# Ethernet.net
KiCad netlist of a schematic drawn in Altium Designer
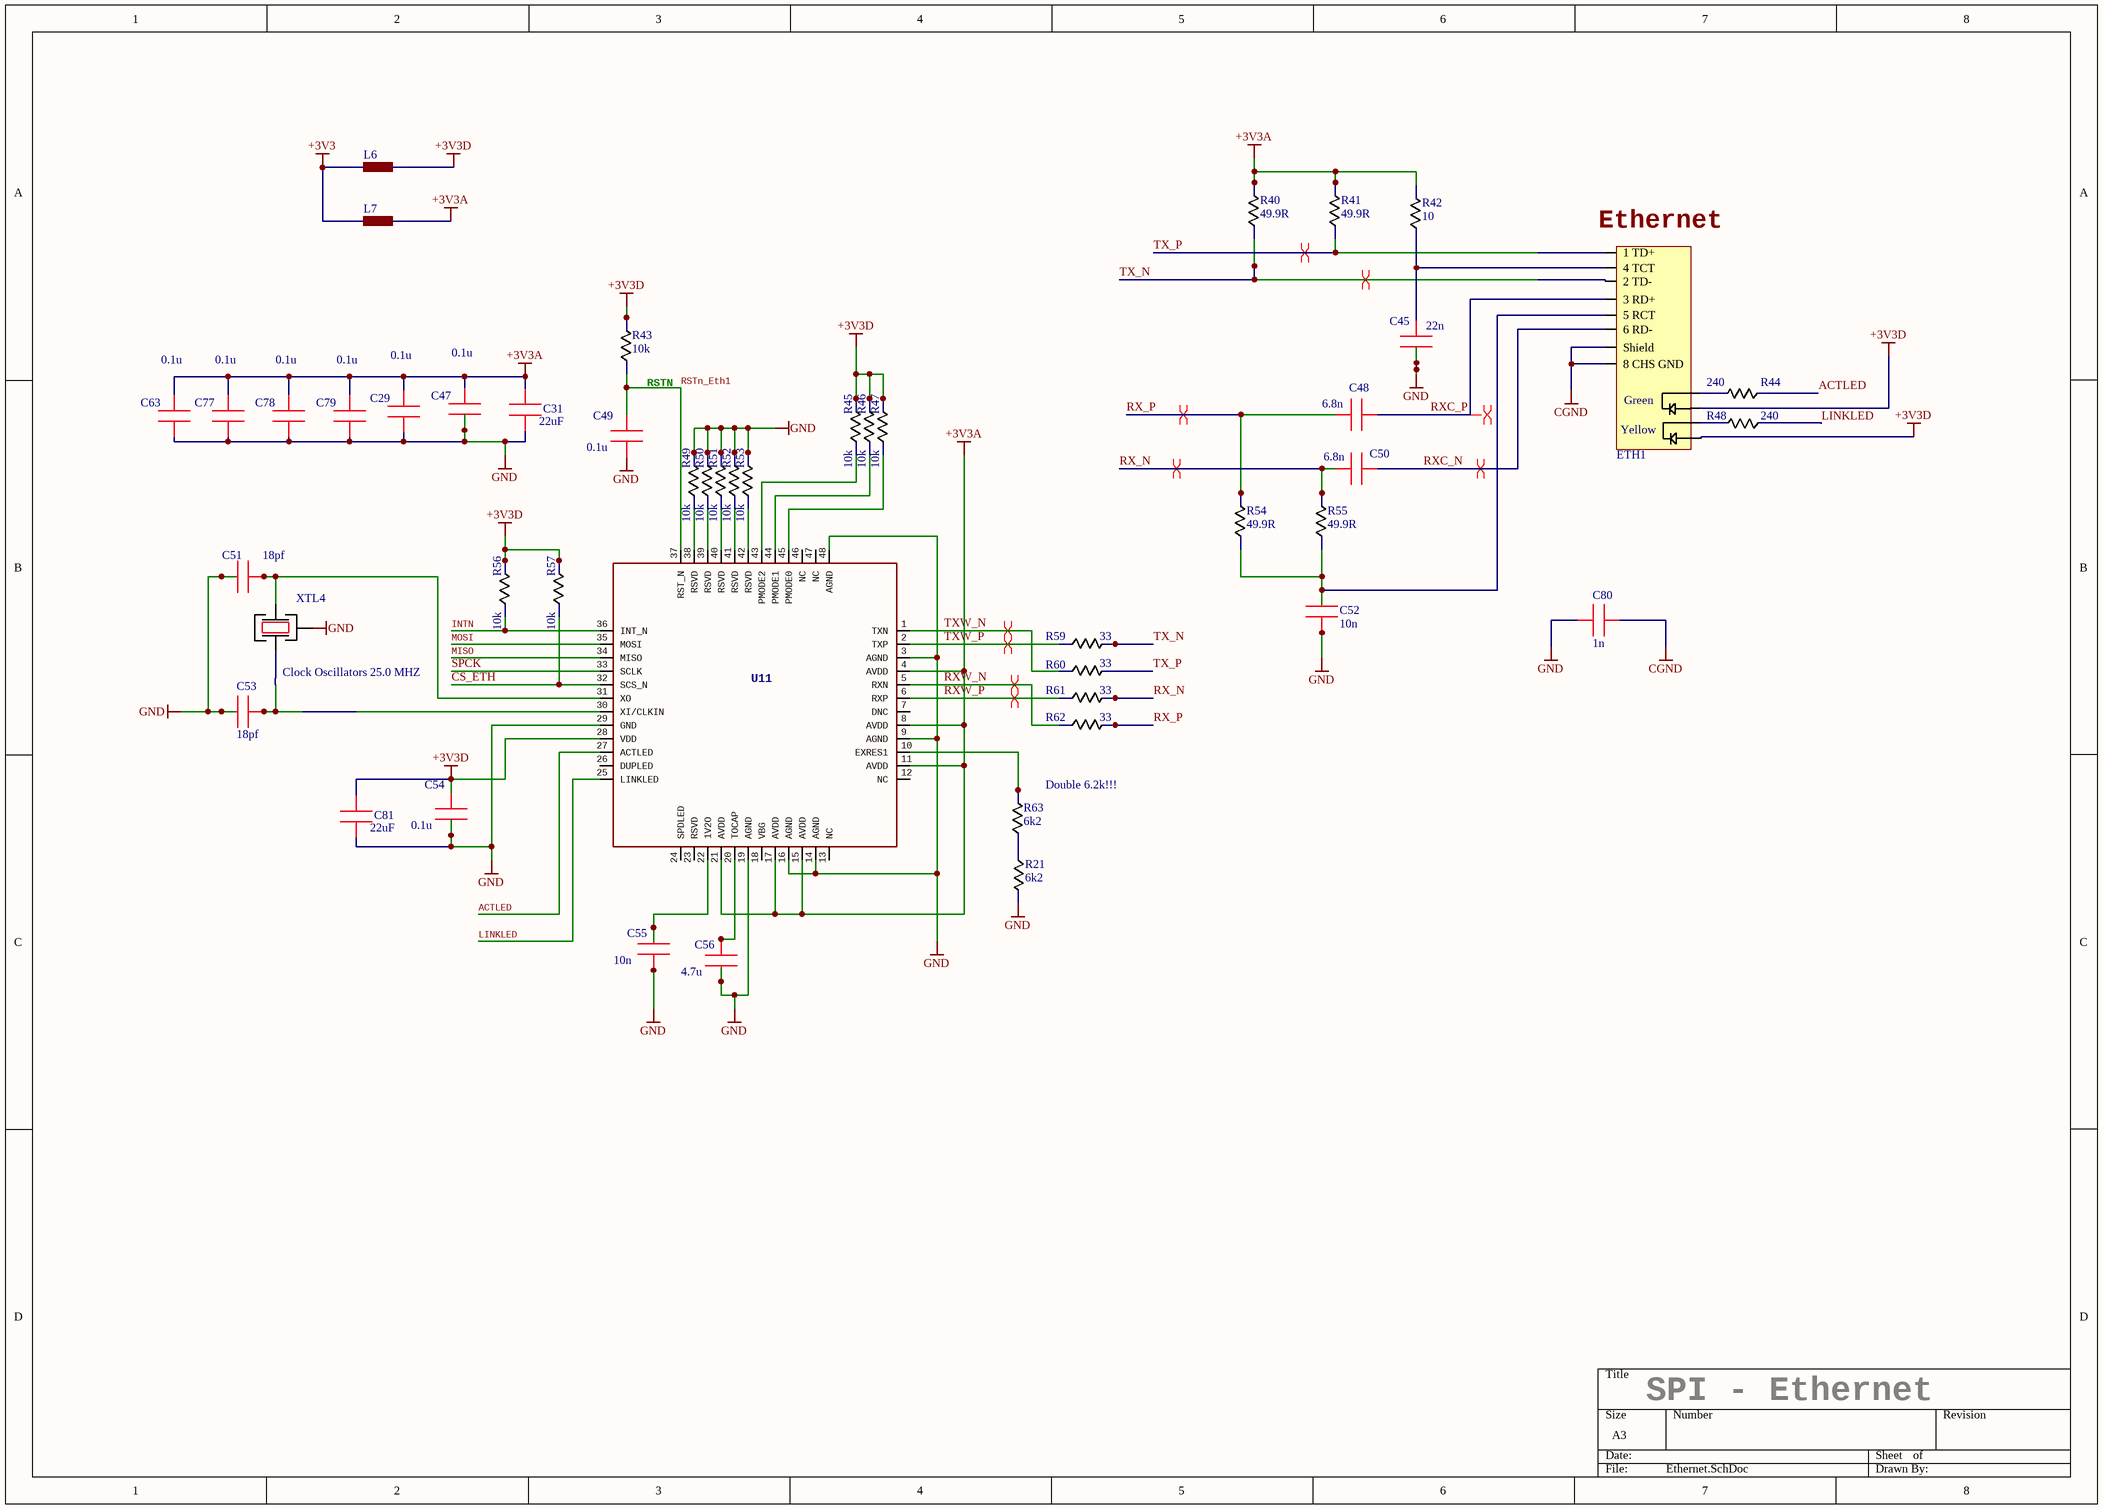
[diagram p0: Ethernet.SchDoc]

(export (version "E")
  (design (tool "Eeschema 10.0.6"))
  (components
    (comp (ref "C29")
      (value "0.1u")
      (footprint "0603")
      (fields (field (name "PART NUMBER") "GRM188R72A104KA35D"))
      (libsource (lib "kontr") (part "0603 CAP"))
    )
    (comp (ref "C31")
      (value "22uF")
      (footprint "1206")
      (fields (field (name "PART NUMBER") "CC1206KKX5R7BB226"))
      (libsource (lib "kontr") (part "0805 Cap"))
    )
    (comp (ref "C45")
      (value "22n")
      (footprint "0603")
      (fields (field (name "PART NUMBER") "GRM188R71H223KA01D"))
      (libsource (lib "kontr") (part "0603 CAP"))
    )
    (comp (ref "C47")
      (value "0.1u")
      (footprint "0603")
      (fields (field (name "PART NUMBER") "GRM188R72A104KA35D"))
      (libsource (lib "kontr") (part "0603 CAP"))
    )
    (comp (ref "C48")
      (value "6.8n")
      (footprint "0603")
      (fields (field (name "PART NUMBER") "CC0603KRX7R9BB682"))
      (libsource (lib "kontr") (part "0603 CAP"))
    )
    (comp (ref "C49")
      (value "0.1u")
      (footprint "0603")
      (fields (field (name "PART NUMBER") "GRM188R72A104KA35D"))
      (libsource (lib "kontr") (part "0603 CAP"))
    )
    (comp (ref "C50")
      (value "6.8n")
      (footprint "0603")
      (fields (field (name "PART NUMBER") "CC0603KRX7R9BB682"))
      (libsource (lib "kontr") (part "0603 CAP"))
    )
    (comp (ref "C51")
      (value "18pf")
      (footprint "0603")
      (fields (field (name "PART NUMBER") "GRM1885C1H180JA01D"))
      (libsource (lib "kontr") (part "0603 CAP"))
    )
    (comp (ref "C52")
      (value "10n")
      (footprint "0603")
      (fields (field (name "PART NUMBER") "CC0603JRX7R9BB103"))
      (libsource (lib "kontr") (part "0603 CAP"))
    )
    (comp (ref "C53")
      (value "18pf")
      (footprint "0603")
      (fields (field (name "PART NUMBER") "GRM1885C1H180JA01D"))
      (libsource (lib "kontr") (part "0603 CAP"))
    )
    (comp (ref "C54")
      (value "0.1u")
      (footprint "0603")
      (fields (field (name "PART NUMBER") "GRM188R72A104KA35D"))
      (libsource (lib "kontr") (part "0603 CAP"))
    )
    (comp (ref "C55")
      (value "10n")
      (footprint "0603")
      (fields (field (name "PART NUMBER") "CC0603JRX7R9BB103"))
      (libsource (lib "kontr") (part "0603 CAP"))
    )
    (comp (ref "C56")
      (value "4.7u")
      (footprint "0603")
      (fields (field (name "PART NUMBER") "CC0603KRX5R7BB475"))
      (libsource (lib "kontr") (part "0603 CAP"))
    )
    (comp (ref "C63")
      (value "0.1u")
      (footprint "0603")
      (fields (field (name "PART NUMBER") "GRM188R72A104KA35D"))
      (libsource (lib "kontr") (part "0603 CAP"))
    )
    (comp (ref "C77")
      (value "0.1u")
      (footprint "0603")
      (fields (field (name "PART NUMBER") "GRM188R72A104KA35D"))
      (libsource (lib "kontr") (part "0603 CAP"))
    )
    (comp (ref "C78")
      (value "0.1u")
      (footprint "0603")
      (fields (field (name "PART NUMBER") "GRM188R72A104KA35D"))
      (libsource (lib "kontr") (part "0603 CAP"))
    )
    (comp (ref "C79")
      (value "0.1u")
      (footprint "0603")
      (fields (field (name "PART NUMBER") "GRM188R72A104KA35D"))
      (libsource (lib "kontr") (part "0603 CAP"))
    )
    (comp (ref "C80")
      (value "1n")
      (footprint "1206")
      (fields (field (name "PART NUMBER") "CC1206KKX7RDBB102"))
      (libsource (lib "kontr") (part "0603 CAP"))
    )
    (comp (ref "C81")
      (value "22uF")
      (footprint "1206")
      (fields (field (name "PART NUMBER") "CC1206KKX5R7BB226"))
      (libsource (lib "kontr") (part "0805 Cap"))
    )
    (comp (ref "ETH1")
      (value "~")
      (footprint "RJ45")
      (fields (field (name "PART NUMBER") "J0011D21BNL"))
      (libsource (lib "kontr") (part "J0011D21BNL"))
    )
    (comp (ref "L6")
      (value "~")
      (footprint "0805")
      (fields (field (name "PART NUMBER") "BLM41PG102SN1L"))
      (libsource (lib "altium-import") (part "root_0__kontr.SCHLIB"))
    )
    (comp (ref "L7")
      (value "~")
      (footprint "0805")
      (fields (field (name "PART NUMBER") "BLM41PG102SN1L"))
      (libsource (lib "altium-import") (part "root_0__kontr.SCHLIB"))
    )
    (comp (ref "R21")
      (value "6k2")
      (footprint "0603")
      (fields (field (name "PART NUMBER") "RC0603JR-076K2L"))
      (libsource (lib "kontr") (part "Resistor 0805"))
    )
    (comp (ref "R40")
      (value "49.9R")
      (footprint "0603")
      (fields (field (name "PART NUMBER") "RC0603FR-0749R9"))
      (libsource (lib "kontr") (part "0603 RES"))
    )
    (comp (ref "R41")
      (value "49.9R")
      (footprint "0603")
      (fields (field (name "PART NUMBER") "RC0603FR-0749R9"))
      (libsource (lib "kontr") (part "0603 RES"))
    )
    (comp (ref "R42")
      (value "10")
      (footprint "0603")
      (fields (field (name "PART NUMBER") "CRCW060310R0FKEA"))
      (libsource (lib "kontr") (part "0603 RES"))
    )
    (comp (ref "R43")
      (value "10k")
      (footprint "0603")
      (fields (field (name "PART NUMBER") "RC0603JR-0710K"))
      (libsource (lib "kontr") (part "0603 RES"))
    )
    (comp (ref "R44")
      (value "240")
      (footprint "0603")
      (fields (field (name "PART NUMBER") "RC0603FR-07240RL"))
      (libsource (lib "kontr") (part "0603 RES"))
    )
    (comp (ref "R45")
      (value "10k")
      (footprint "0603")
      (fields (field (name "PART NUMBER") "RC0603JR-0710K"))
      (libsource (lib "kontr") (part "0603 RES"))
    )
    (comp (ref "R46")
      (value "10k")
      (footprint "0603")
      (fields (field (name "PART NUMBER") "RC0603JR-0710K"))
      (libsource (lib "kontr") (part "0603 RES"))
    )
    (comp (ref "R47")
      (value "10k")
      (footprint "0603")
      (fields (field (name "PART NUMBER") "RC0603JR-0710K"))
      (libsource (lib "kontr") (part "0603 RES"))
    )
    (comp (ref "R48")
      (value "240")
      (footprint "0603")
      (fields (field (name "PART NUMBER") "RC0603FR-07240RL"))
      (libsource (lib "kontr") (part "0603 RES"))
    )
    (comp (ref "R49")
      (value "10k")
      (footprint "0603")
      (fields (field (name "PART NUMBER") "RC0603JR-0710K"))
      (libsource (lib "kontr") (part "0603 RES"))
    )
    (comp (ref "R50")
      (value "10k")
      (footprint "0603")
      (fields (field (name "PART NUMBER") "RC0603JR-0710K"))
      (libsource (lib "kontr") (part "0603 RES"))
    )
    (comp (ref "R51")
      (value "10k")
      (footprint "0603")
      (fields (field (name "PART NUMBER") "RC0603JR-0710K"))
      (libsource (lib "kontr") (part "0603 RES"))
    )
    (comp (ref "R52")
      (value "10k")
      (footprint "0603")
      (fields (field (name "PART NUMBER") "RC0603JR-0710K"))
      (libsource (lib "kontr") (part "0603 RES"))
    )
    (comp (ref "R53")
      (value "10k")
      (footprint "0603")
      (fields (field (name "PART NUMBER") "RC0603JR-0710K"))
      (libsource (lib "kontr") (part "0603 RES"))
    )
    (comp (ref "R54")
      (value "49.9R")
      (footprint "0603")
      (fields (field (name "PART NUMBER") "RC0603FR-0749R9"))
      (libsource (lib "kontr") (part "0603 RES"))
    )
    (comp (ref "R55")
      (value "49.9R")
      (footprint "0603")
      (fields (field (name "PART NUMBER") "RC0603FR-0749R9"))
      (libsource (lib "kontr") (part "0603 RES"))
    )
    (comp (ref "R56")
      (value "10k")
      (footprint "0603")
      (fields (field (name "PART NUMBER") "RC0603JR-0710K"))
      (libsource (lib "kontr") (part "0603 RES"))
    )
    (comp (ref "R57")
      (value "10k")
      (footprint "0603")
      (fields (field (name "PART NUMBER") "RC0603JR-0710K"))
      (libsource (lib "kontr") (part "0603 RES"))
    )
    (comp (ref "R59")
      (value "33")
      (footprint "0603")
      (fields (field (name "PART NUMBER") "RC0603FR-0733RL"))
      (libsource (lib "kontr") (part "0603 RES"))
    )
    (comp (ref "R60")
      (value "33")
      (footprint "0603")
      (fields (field (name "PART NUMBER") "RC0603FR-0733RL"))
      (libsource (lib "kontr") (part "0603 RES"))
    )
    (comp (ref "R61")
      (value "33")
      (footprint "0603")
      (fields (field (name "PART NUMBER") "RC0603FR-0733RL"))
      (libsource (lib "kontr") (part "0603 RES"))
    )
    (comp (ref "R62")
      (value "33")
      (footprint "0603")
      (fields (field (name "PART NUMBER") "RC0603FR-0733RL"))
      (libsource (lib "kontr") (part "0603 RES"))
    )
    (comp (ref "R63")
      (value "6k2")
      (footprint "0603")
      (fields (field (name "PART NUMBER") "RC0603JR-076K2L"))
      (libsource (lib "kontr") (part "0603 RES"))
    )
    (comp (ref "U11")
      (value "~")
      (footprint "LQFP 48")
      (fields (field (name "PART NUMBER") "W5500"))
      (libsource (lib "W5500") (part "W5500"))
    )
    (comp (ref "XTL4")
      (value "~")
      (footprint "KX-7 XTAL")
      (fields
        (field (name "PART DESCRIPTION") "Clock Oscillators 25.0 MHZ")
        (field (name "PART NUMBER") "Geyer KX-7 25.0 MHz")
      )
      (libsource (lib "kontr") (part "KX-7"))
    )
  )
  (nets
    (net (code "1") (name "+3V3") (class "Default")
      (node (ref "L6") (pin "1") (pintype "passive"))
      (node (ref "L7") (pin "1") (pintype "passive"))
    )
    (net (code "2") (name "+3V3A") (class "Default")
      (node (ref "C29") (pin "1") (pinfunction "1_1") (pintype "passive"))
      (node (ref "C31") (pin "2") (pinfunction "2_2") (pintype "passive"))
      (node (ref "C47") (pin "1") (pinfunction "1_1") (pintype "passive"))
      (node (ref "C63") (pin "1") (pinfunction "1_1") (pintype "passive"))
      (node (ref "C77") (pin "1") (pinfunction "1_1") (pintype "passive"))
      (node (ref "C78") (pin "1") (pinfunction "1_1") (pintype "passive"))
      (node (ref "C79") (pin "1") (pinfunction "1_1") (pintype "passive"))
      (node (ref "L7") (pin "2") (pintype "passive"))
      (node (ref "R40") (pin "2") (pintype "passive"))
      (node (ref "R41") (pin "2") (pintype "passive"))
      (node (ref "R42") (pin "2") (pintype "passive"))
      (node (ref "U11") (pin "11") (pinfunction "AVDD_11") (pintype "passive"))
      (node (ref "U11") (pin "15") (pinfunction "AVDD_15") (pintype "passive"))
      (node (ref "U11") (pin "17") (pinfunction "AVDD_17") (pintype "passive"))
      (node (ref "U11") (pin "21") (pinfunction "AVDD_21") (pintype "passive"))
      (node (ref "U11") (pin "4") (pinfunction "AVDD_4") (pintype "passive"))
      (node (ref "U11") (pin "8") (pinfunction "AVDD_8") (pintype "passive"))
    )
    (net (code "3") (name "+3V3D") (class "Default")
      (node (ref "C54") (pin "1") (pinfunction "1_1") (pintype "passive"))
      (node (ref "C81") (pin "2") (pinfunction "2_2") (pintype "passive"))
      (node (ref "ETH1") (pin "12") (pinfunction "LDYE_12") (pintype "passive"))
      (node (ref "ETH1") (pin "9") (pinfunction "LDGr_9") (pintype "passive"))
      (node (ref "L6") (pin "2") (pintype "passive"))
      (node (ref "R43") (pin "2") (pintype "passive"))
      (node (ref "R45") (pin "2") (pintype "passive"))
      (node (ref "R46") (pin "2") (pintype "passive"))
      (node (ref "R47") (pin "2") (pintype "passive"))
      (node (ref "R56") (pin "2") (pintype "passive"))
      (node (ref "R57") (pin "2") (pintype "passive"))
      (node (ref "U11") (pin "28") (pinfunction "VDD_28") (pintype "passive"))
    )
    (net (code "4") (name "/ACTLED") (class "Default")
      (node (ref "R44") (pin "1") (pintype "passive"))
      (node (ref "U11") (pin "27") (pinfunction "ACTLED_27") (pintype "passive"))
    )
    (net (code "5") (name "/CS_ETH") (class "Default")
      (node (ref "R57") (pin "1") (pintype "passive"))
      (node (ref "U11") (pin "32") (pinfunction "SCS_N_32") (pintype "passive"))
    )
    (net (code "6") (name "/INTN") (class "Default")
      (node (ref "R56") (pin "1") (pintype "passive"))
      (node (ref "U11") (pin "36") (pinfunction "INT_N_36") (pintype "passive"))
    )
    (net (code "7") (name "/LINKLED") (class "Default")
      (node (ref "R48") (pin "1") (pintype "passive"))
      (node (ref "U11") (pin "25") (pinfunction "LINKLED_25") (pintype "passive"))
    )
    (net (code "8") (name "/MISO") (class "Default")
      (node (ref "U11") (pin "34") (pinfunction "MISO_34") (pintype "passive"))
    )
    (net (code "9") (name "/MOSI") (class "Default")
      (node (ref "U11") (pin "35") (pinfunction "MOSI_35") (pintype "passive"))
    )
    (net (code "10") (name "/RSTn_Eth1") (class "Default")
      (node (ref "C49") (pin "1") (pinfunction "1_1") (pintype "passive"))
      (node (ref "R43") (pin "1") (pintype "passive"))
      (node (ref "U11") (pin "37") (pinfunction "RST_N_37") (pintype "passive"))
    )
    (net (code "11") (name "/RXC_N") (class "Default")
      (node (ref "C50") (pin "2") (pinfunction "2_2") (pintype "passive"))
      (node (ref "ETH1") (pin "6") (pinfunction "6_RD-_6") (pintype "passive"))
    )
    (net (code "12") (name "/RXC_P") (class "Default")
      (node (ref "C48") (pin "2") (pinfunction "2_2") (pintype "passive"))
      (node (ref "ETH1") (pin "3") (pinfunction "3_RD+_3") (pintype "passive"))
    )
    (net (code "13") (name "/RXW_N") (class "Default")
      (node (ref "R62") (pin "1") (pintype "passive"))
      (node (ref "U11") (pin "5") (pinfunction "RXN_5") (pintype "passive"))
    )
    (net (code "14") (name "/RXW_P") (class "Default")
      (node (ref "R61") (pin "1") (pintype "passive"))
      (node (ref "U11") (pin "6") (pinfunction "RXP_6") (pintype "passive"))
    )
    (net (code "15") (name "/RX_N") (class "Default")
      (node (ref "C50") (pin "1") (pinfunction "1_1") (pintype "passive"))
      (node (ref "R55") (pin "2") (pintype "passive"))
      (node (ref "R61") (pin "2") (pintype "passive"))
    )
    (net (code "16") (name "/RX_P") (class "Default")
      (node (ref "C48") (pin "1") (pinfunction "1_1") (pintype "passive"))
      (node (ref "R54") (pin "2") (pintype "passive"))
      (node (ref "R62") (pin "2") (pintype "passive"))
    )
    (net (code "17") (name "/SPCK") (class "Default")
      (node (ref "U11") (pin "33") (pinfunction "SCLK_33") (pintype "passive"))
    )
    (net (code "18") (name "/TXW_N") (class "Default")
      (node (ref "R60") (pin "1") (pintype "passive"))
      (node (ref "U11") (pin "1") (pinfunction "TXN_1") (pintype "passive"))
    )
    (net (code "19") (name "/TXW_P") (class "Default")
      (node (ref "R59") (pin "1") (pintype "passive"))
      (node (ref "U11") (pin "2") (pinfunction "TXP_2") (pintype "passive"))
    )
    (net (code "20") (name "/TX_N") (class "Default")
      (node (ref "ETH1") (pin "2") (pinfunction "2_TD-_2") (pintype "passive"))
      (node (ref "R40") (pin "1") (pintype "passive"))
      (node (ref "R59") (pin "2") (pintype "passive"))
    )
    (net (code "21") (name "/TX_P") (class "Default")
      (node (ref "ETH1") (pin "1") (pinfunction "1_TD+_1") (pintype "passive"))
      (node (ref "R41") (pin "1") (pintype "passive"))
      (node (ref "R60") (pin "2") (pintype "passive"))
    )
    (net (code "22") (name "CGND") (class "Default")
      (node (ref "C80") (pin "2") (pinfunction "2_2") (pintype "passive"))
      (node (ref "ETH1") (pin "8") (pinfunction "8_CHS_GND_8") (pintype "passive"))
      (node (ref "ETH1") (pin "SHIELD") (pinfunction "Shield_SHIELD") (pintype "passive"))
    )
    (net (code "23") (name "GND") (class "Default")
      (node (ref "C29") (pin "2") (pinfunction "2_2") (pintype "passive"))
      (node (ref "C31") (pin "1") (pinfunction "1_1") (pintype "passive"))
      (node (ref "C45") (pin "2") (pinfunction "2_2") (pintype "passive"))
      (node (ref "C47") (pin "2") (pinfunction "2_2") (pintype "passive"))
      (node (ref "C49") (pin "2") (pinfunction "2_2") (pintype "passive"))
      (node (ref "C51") (pin "1") (pinfunction "1_1") (pintype "passive"))
      (node (ref "C52") (pin "2") (pinfunction "2_2") (pintype "passive"))
      (node (ref "C53") (pin "1") (pinfunction "1_1") (pintype "passive"))
      (node (ref "C54") (pin "2") (pinfunction "2_2") (pintype "passive"))
      (node (ref "C55") (pin "2") (pinfunction "2_2") (pintype "passive"))
      (node (ref "C56") (pin "2") (pinfunction "2_2") (pintype "passive"))
      (node (ref "C63") (pin "2") (pinfunction "2_2") (pintype "passive"))
      (node (ref "C77") (pin "2") (pinfunction "2_2") (pintype "passive"))
      (node (ref "C78") (pin "2") (pinfunction "2_2") (pintype "passive"))
      (node (ref "C79") (pin "2") (pinfunction "2_2") (pintype "passive"))
      (node (ref "C80") (pin "1") (pinfunction "1_1") (pintype "passive"))
      (node (ref "C81") (pin "1") (pinfunction "1_1") (pintype "passive"))
      (node (ref "R21") (pin "2") (pintype "passive"))
      (node (ref "R49") (pin "2") (pintype "passive"))
      (node (ref "R50") (pin "2") (pintype "passive"))
      (node (ref "R51") (pin "2") (pintype "passive"))
      (node (ref "R52") (pin "2") (pintype "passive"))
      (node (ref "R53") (pin "2") (pintype "passive"))
      (node (ref "U11") (pin "14") (pinfunction "AGND_14") (pintype "passive"))
      (node (ref "U11") (pin "16") (pinfunction "AGND_16") (pintype "passive"))
      (node (ref "U11") (pin "19") (pinfunction "AGND_19") (pintype "passive"))
      (node (ref "U11") (pin "29") (pinfunction "GND_29") (pintype "passive"))
      (node (ref "U11") (pin "3") (pinfunction "AGND_3") (pintype "passive"))
      (node (ref "U11") (pin "48") (pinfunction "AGND_48") (pintype "passive"))
      (node (ref "U11") (pin "9") (pinfunction "AGND_9") (pintype "passive"))
      (node (ref "XTL4") (pin "2") (pinfunction "2_2") (pintype "passive"))
    )
    (net (code "24") (name "Net-(ETH1-4_TCT)") (class "Default")
      (node (ref "C45") (pin "1") (pinfunction "1_1") (pintype "passive"))
      (node (ref "ETH1") (pin "4") (pinfunction "4_TCT_4") (pintype "passive"))
      (node (ref "R42") (pin "1") (pintype "passive"))
    )
    (net (code "25") (name "Net-(ETH1-5_RCT)") (class "Default")
      (node (ref "C52") (pin "1") (pinfunction "1_1") (pintype "passive"))
      (node (ref "ETH1") (pin "5") (pinfunction "5_RCT_5") (pintype "passive"))
      (node (ref "R54") (pin "1") (pintype "passive"))
      (node (ref "R55") (pin "1") (pintype "passive"))
    )
    (net (code "26") (name "Net-(ETH1-LDGr-Pad10)") (class "Default")
      (node (ref "ETH1") (pin "10") (pinfunction "LDGr_10") (pintype "passive"))
      (node (ref "R44") (pin "2") (pintype "passive"))
    )
    (net (code "27") (name "Net-(ETH1-LDYE-Pad11)") (class "Default")
      (node (ref "ETH1") (pin "11") (pinfunction "LDYE_11") (pintype "passive"))
      (node (ref "R48") (pin "2") (pintype "passive"))
    )
    (net (code "28") (name "Net-(R21-Pad1)") (class "Default")
      (node (ref "R21") (pin "1") (pintype "passive"))
      (node (ref "R63") (pin "1") (pintype "passive"))
    )
    (net (code "29") (name "Net-(R49-Pad1)") (class "Default")
      (node (ref "R49") (pin "1") (pintype "passive"))
      (node (ref "U11") (pin "38") (pinfunction "RSVD_38") (pintype "passive"))
    )
    (net (code "30") (name "Net-(R50-Pad1)") (class "Default")
      (node (ref "R50") (pin "1") (pintype "passive"))
      (node (ref "U11") (pin "39") (pinfunction "RSVD_39") (pintype "passive"))
    )
    (net (code "31") (name "Net-(R51-Pad1)") (class "Default")
      (node (ref "R51") (pin "1") (pintype "passive"))
      (node (ref "U11") (pin "40") (pinfunction "RSVD_40") (pintype "passive"))
    )
    (net (code "32") (name "Net-(R52-Pad1)") (class "Default")
      (node (ref "R52") (pin "1") (pintype "passive"))
      (node (ref "U11") (pin "41") (pinfunction "RSVD_41") (pintype "passive"))
    )
    (net (code "33") (name "Net-(R53-Pad1)") (class "Default")
      (node (ref "R53") (pin "1") (pintype "passive"))
      (node (ref "U11") (pin "42") (pinfunction "RSVD_42") (pintype "passive"))
    )
    (net (code "34") (name "Net-(U11-1V2O)") (class "Default")
      (node (ref "C55") (pin "1") (pinfunction "1_1") (pintype "passive"))
      (node (ref "U11") (pin "22") (pinfunction "1V2O_22") (pintype "passive"))
    )
    (net (code "35") (name "Net-(U11-EXRES1)") (class "Default")
      (node (ref "R63") (pin "2") (pintype "passive"))
      (node (ref "U11") (pin "10") (pinfunction "EXRES1_10") (pintype "passive"))
    )
    (net (code "36") (name "Net-(U11-PMODE0)") (class "Default")
      (node (ref "R47") (pin "1") (pintype "passive"))
      (node (ref "U11") (pin "45") (pinfunction "PMODE0_45") (pintype "passive"))
    )
    (net (code "37") (name "Net-(U11-PMODE1)") (class "Default")
      (node (ref "R46") (pin "1") (pintype "passive"))
      (node (ref "U11") (pin "44") (pinfunction "PMODE1_44") (pintype "passive"))
    )
    (net (code "38") (name "Net-(U11-PMODE2)") (class "Default")
      (node (ref "R45") (pin "1") (pintype "passive"))
      (node (ref "U11") (pin "43") (pinfunction "PMODE2_43") (pintype "passive"))
    )
    (net (code "39") (name "Net-(U11-TOCAP)") (class "Default")
      (node (ref "C56") (pin "1") (pinfunction "1_1") (pintype "passive"))
      (node (ref "U11") (pin "20") (pinfunction "TOCAP_20") (pintype "passive"))
    )
    (net (code "40") (name "Net-(U11-XI{slash}CLKIN)") (class "Default")
      (node (ref "C53") (pin "2") (pinfunction "2_2") (pintype "passive"))
      (node (ref "U11") (pin "30") (pinfunction "XI/CLKIN_30") (pintype "passive"))
      (node (ref "XTL4") (pin "1") (pinfunction "5_1") (pintype "passive"))
    )
    (net (code "41") (name "Net-(U11-XO)") (class "Default")
      (node (ref "C51") (pin "2") (pinfunction "2_2") (pintype "passive"))
      (node (ref "U11") (pin "31") (pinfunction "XO_31") (pintype "passive"))
      (node (ref "XTL4") (pin "3") (pinfunction "5_3") (pintype "passive"))
    )
    (net (code "42") (name "unconnected-(U11-DNC-Pad7)") (class "Default")
      (node (ref "U11") (pin "7") (pinfunction "DNC_7") (pintype "passive"))
    )
    (net (code "43") (name "unconnected-(U11-DUPLED-Pad26)") (class "Default")
      (node (ref "U11") (pin "26") (pinfunction "DUPLED_26") (pintype "passive"))
    )
    (net (code "44") (name "unconnected-(U11-NC-Pad12)") (class "Default")
      (node (ref "U11") (pin "12") (pinfunction "NC_12") (pintype "passive"))
    )
    (net (code "45") (name "unconnected-(U11-NC-Pad13)") (class "Default")
      (node (ref "U11") (pin "13") (pinfunction "NC_13") (pintype "passive"))
    )
    (net (code "46") (name "unconnected-(U11-NC-Pad46)") (class "Default")
      (node (ref "U11") (pin "46") (pinfunction "NC_46") (pintype "passive"))
    )
    (net (code "47") (name "unconnected-(U11-NC-Pad47)") (class "Default")
      (node (ref "U11") (pin "47") (pinfunction "NC_47") (pintype "passive"))
    )
    (net (code "48") (name "unconnected-(U11-RSVD-Pad23)") (class "Default")
      (node (ref "U11") (pin "23") (pinfunction "RSVD_23") (pintype "passive"))
    )
    (net (code "49") (name "unconnected-(U11-SPDLED-Pad24)") (class "Default")
      (node (ref "U11") (pin "24") (pinfunction "SPDLED_24") (pintype "passive"))
    )
    (net (code "50") (name "unconnected-(U11-VBG-Pad18)") (class "Default")
      (node (ref "U11") (pin "18") (pinfunction "VBG_18") (pintype "passive"))
    )
  )
)
